# design.net
KiCad netlist of a schematic drawn in Altium Designer
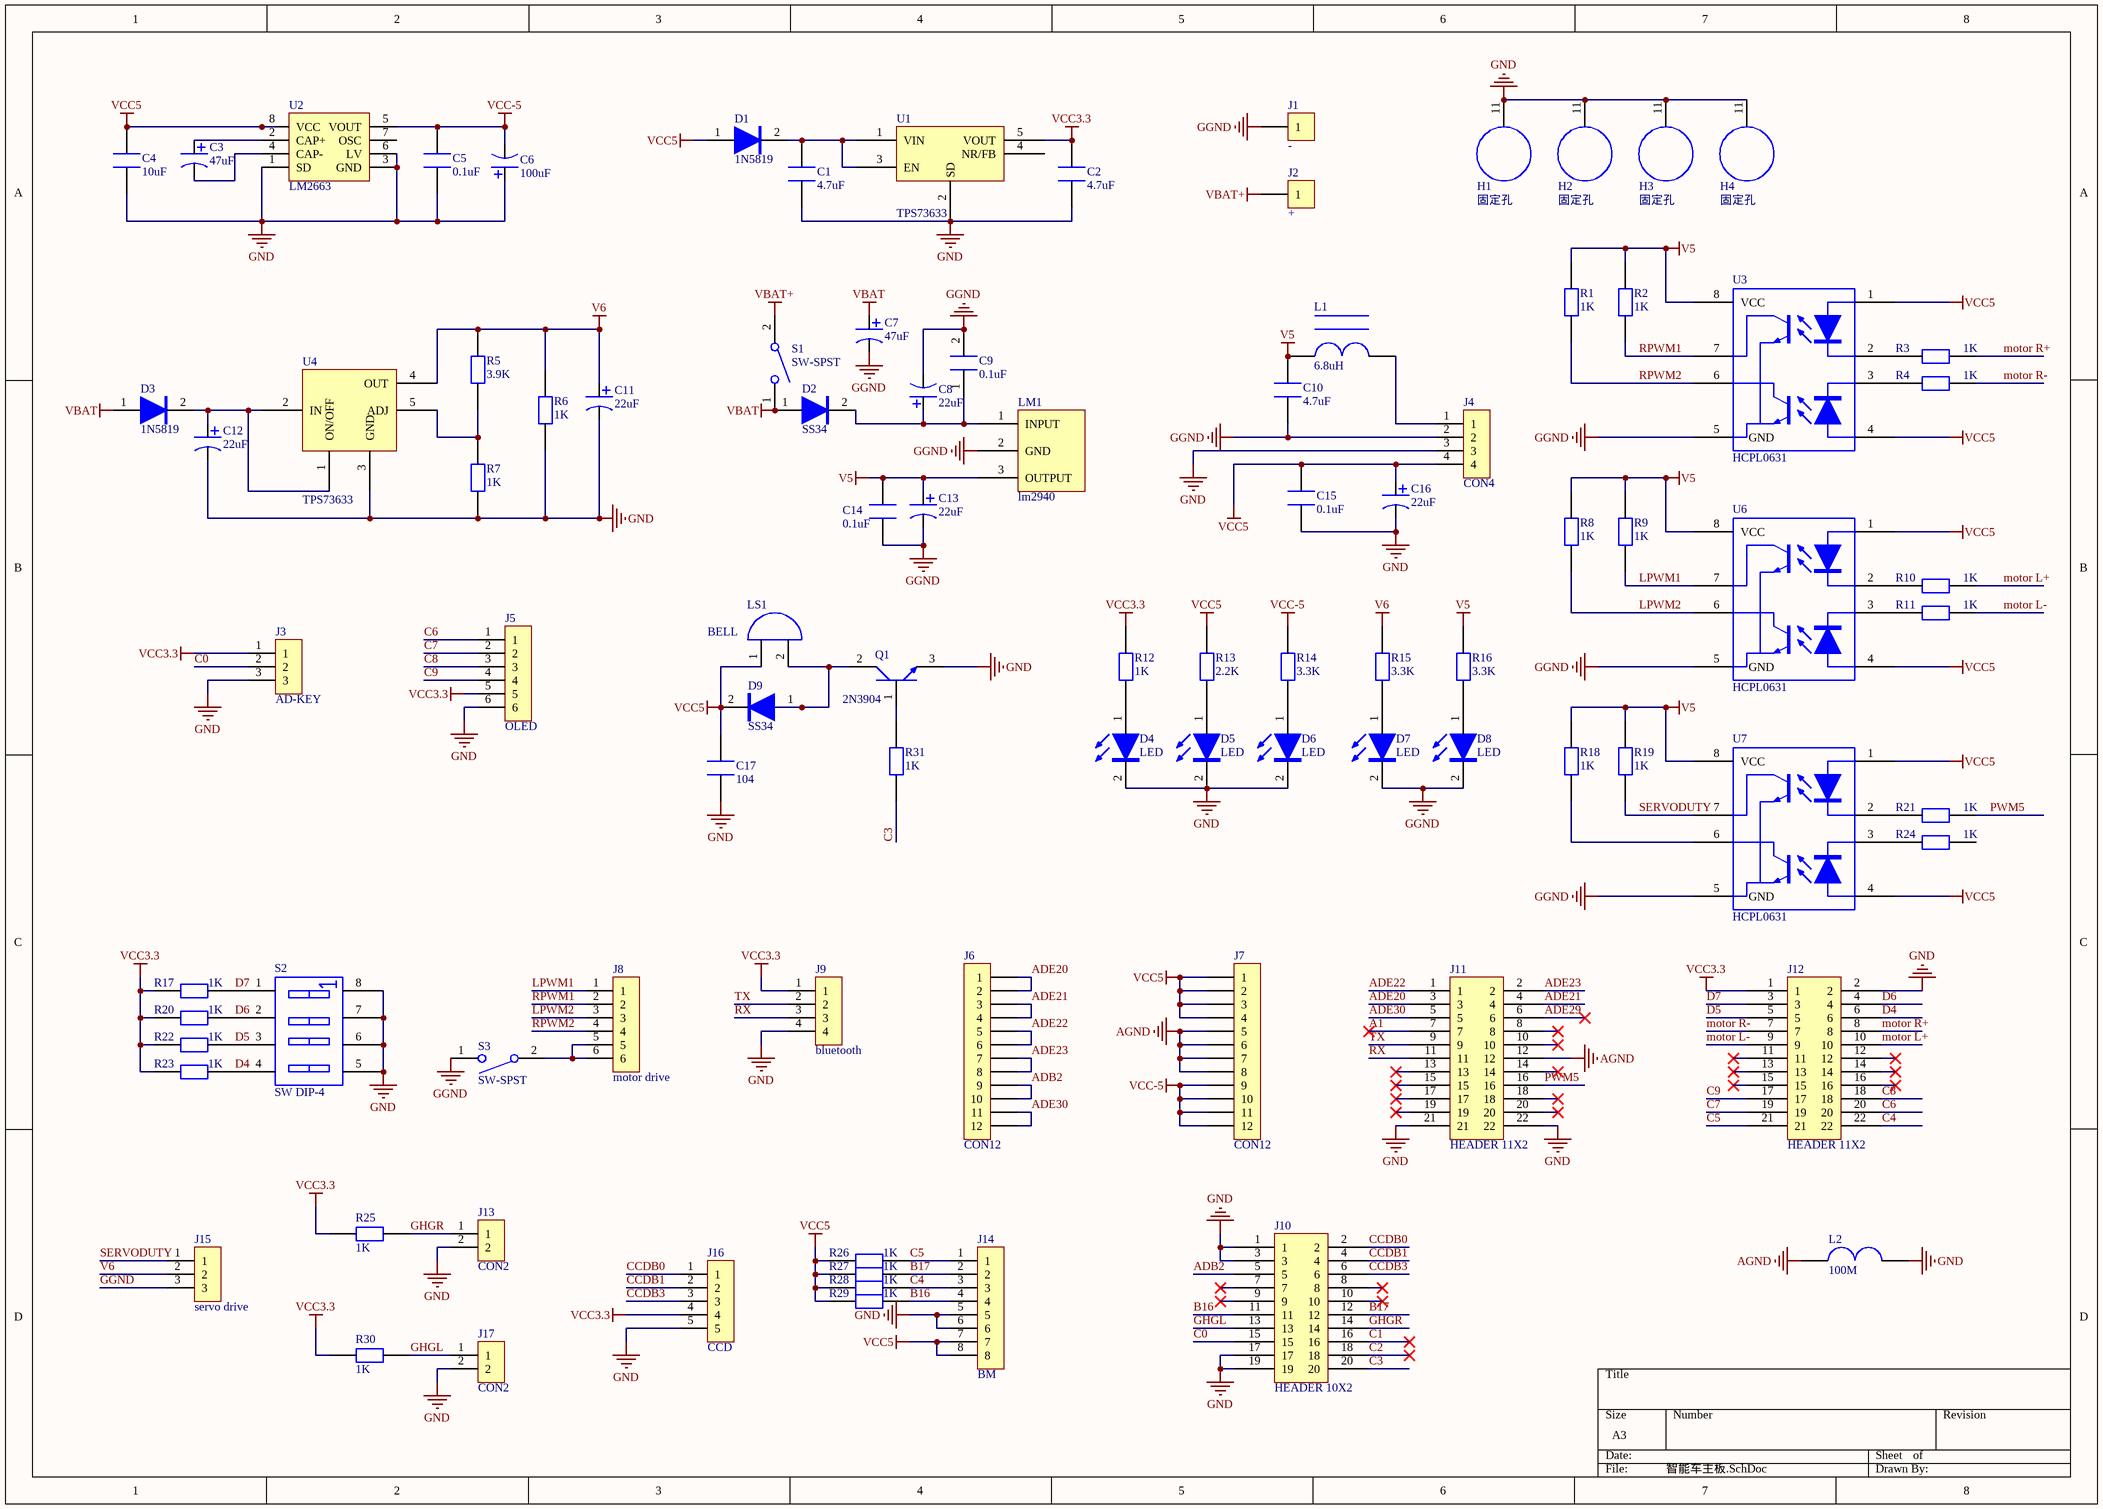
[diagram p0: 智能车主板.SchDoc]

(export (version "E")
  (design (tool "Eeschema 10.0.6"))
  (components
    (comp (ref "C1")
      (value "4.7uF")
      (footprint "0805_Res")
      (description "电容")
      (libsource (lib "智能车主板") (part "CAP"))
    )
    (comp (ref "C2")
      (value "4.7uF")
      (footprint "0805_Res")
      (description "电容")
      (libsource (lib "智能车主板") (part "CAP"))
    )
    (comp (ref "C3")
      (value "47uF")
      (footprint "C型钽电容_6032_28")
      (description "极性电容")
      (libsource (lib "智能车主板") (part "极性电容"))
    )
    (comp (ref "C4")
      (value "10uF")
      (footprint "0805_Res")
      (description "电容")
      (libsource (lib "智能车主板") (part "CAP"))
    )
    (comp (ref "C5")
      (value "0.1uF")
      (footprint "0805_Res")
      (description "电容")
      (libsource (lib "智能车主板") (part "CAP"))
    )
    (comp (ref "C6")
      (value "100uF")
      (footprint "D型钽电容_7343_31")
      (description "极性电容")
      (libsource (lib "智能车主板") (part "极性电容"))
    )
    (comp (ref "C7")
      (value "47uF")
      (footprint "D型钽电容_7343_31")
      (description "极性电容")
      (libsource (lib "智能车主板") (part "极性电容"))
    )
    (comp (ref "C8")
      (value "22uF")
      (footprint "C型钽电容_6032_28")
      (description "极性电容")
      (libsource (lib "智能车主板") (part "极性电容"))
    )
    (comp (ref "C9")
      (value "0.1uF")
      (footprint "0805_Res")
      (description "电容")
      (libsource (lib "") (part "CAP_1"))
    )
    (comp (ref "C10")
      (value "4.7uF")
      (footprint "0805_Res")
      (description "电容")
      (libsource (lib "智能车主板") (part "CAP"))
    )
    (comp (ref "C11")
      (value "22uF")
      (footprint "D型钽电容_7343_31")
      (description "极性电容")
      (libsource (lib "智能车主板") (part "极性电容"))
    )
    (comp (ref "C12")
      (value "22uF")
      (footprint "D型钽电容_7343_31")
      (description "极性电容")
      (libsource (lib "智能车主板") (part "极性电容"))
    )
    (comp (ref "C13")
      (value "22uF")
      (footprint "D型钽电容_7343_31")
      (description "极性电容")
      (libsource (lib "智能车主板") (part "极性电容"))
    )
    (comp (ref "C14")
      (value "0.1uF")
      (footprint "0805_Res")
      (description "电容")
      (libsource (lib "智能车主板") (part "CAP"))
    )
    (comp (ref "C15")
      (value "0.1uF")
      (footprint "0805_Res")
      (description "电容")
      (libsource (lib "智能车主板") (part "CAP"))
    )
    (comp (ref "C16")
      (value "22uF")
      (footprint "D型钽电容_7343_31")
      (description "极性电容")
      (libsource (lib "智能车主板") (part "极性电容"))
    )
    (comp (ref "C17")
      (value "104")
      (footprint "0805_RES")
      (description "电容")
      (libsource (lib "智能车主板") (part "CAP"))
    )
    (comp (ref "D1")
      (value "1N5819")
      (footprint "0805_Dio")
      (description "二极管")
      (libsource (lib "智能车主板") (part "SS34"))
    )
    (comp (ref "D2")
      (value "SS34")
      (footprint "0805_Dio")
      (description "二极管")
      (libsource (lib "智能车主板") (part "SS34"))
    )
    (comp (ref "D3")
      (value "1N5819")
      (footprint "0805_Dio")
      (description "二极管")
      (libsource (lib "智能车主板") (part "SS34"))
    )
    (comp (ref "D4")
      (value "LED")
      (footprint "0805_Dio")
      (description "LED灯")
      (libsource (lib "智能车主板") (part "LED"))
    )
    (comp (ref "D5")
      (value "LED")
      (footprint "0805_Dio")
      (description "LED灯")
      (libsource (lib "智能车主板") (part "LED"))
    )
    (comp (ref "D6")
      (value "LED")
      (footprint "0805_Dio")
      (description "LED灯")
      (libsource (lib "智能车主板") (part "LED"))
    )
    (comp (ref "D7")
      (value "LED")
      (footprint "0805_Dio")
      (description "LED灯")
      (libsource (lib "智能车主板") (part "LED"))
    )
    (comp (ref "D8")
      (value "LED")
      (footprint "0805_Dio")
      (description "LED灯")
      (libsource (lib "智能车主板") (part "LED"))
    )
    (comp (ref "D9")
      (value "SS34")
      (footprint "SS34_3D")
      (description "二极管")
      (libsource (lib "智能车主板") (part "SS34"))
    )
    (comp (ref "H1") (value "固定孔") (footprint "铜柱孔3") (libsource (lib "智能车主板") (part "固定孔")))
    (comp (ref "H2") (value "固定孔") (footprint "铜柱孔3") (libsource (lib "智能车主板") (part "固定孔")))
    (comp (ref "H3") (value "固定孔") (footprint "铜柱孔3") (libsource (lib "智能车主板") (part "固定孔")))
    (comp (ref "H4") (value "固定孔") (footprint "铜柱孔3") (libsource (lib "智能车主板") (part "固定孔")))
    (comp (ref "J1")
      (value "-")
      (footprint "单面焊盘2*3MM_1PIN")
      (description "排针")
      (libsource (lib "智能车主板") (part "CON1"))
    )
    (comp (ref "J2")
      (value "+")
      (footprint "单面焊盘2*3MM_1PIN")
      (description "排针")
      (libsource (lib "智能车主板") (part "CON1"))
    )
    (comp (ref "J3")
      (value "AD-KEY")
      (footprint "HDR1X3")
      (description "排针")
      (libsource (lib "智能车主板") (part "CON3"))
    )
    (comp (ref "J4")
      (value "CON4")
      (footprint "B0505S-2W")
      (description "排针")
      (libsource (lib "智能车主板") (part "CON4"))
    )
    (comp (ref "J5")
      (value "OLED")
      (footprint "HDR1X6")
      (description "排针")
      (libsource (lib "智能车主板") (part "CON6"))
    )
    (comp (ref "J6")
      (value "CON12")
      (footprint "HDR2X6")
      (description "排针")
      (libsource (lib "智能车主板") (part "CON12"))
    )
    (comp (ref "J7")
      (value "CON12")
      (footprint "HDR2X6")
      (description "排针")
      (libsource (lib "") (part "CON12_1"))
    )
    (comp (ref "J8")
      (value "motor drive")
      (footprint "HDR2X3")
      (description "排针")
      (libsource (lib "智能车主板") (part "CON6"))
    )
    (comp (ref "J9")
      (value "bluetooth")
      (footprint "HDR1X4")
      (description "排针")
      (libsource (lib "智能车主板") (part "CON4"))
    )
    (comp (ref "J10")
      (value "HEADER 10X2")
      (footprint "HDR2X10")
      (description "排针")
      (libsource (lib "智能车主板") (part "HEADER 10X2"))
    )
    (comp (ref "J11")
      (value "HEADER 11X2")
      (footprint "HDR2X11")
      (description "排针")
      (libsource (lib "智能车主板") (part "HEADER 11X2"))
    )
    (comp (ref "J12")
      (value "HEADER 11X2")
      (footprint "HDR2X11")
      (description "排针")
      (libsource (lib "智能车主板") (part "HEADER 11X2"))
    )
    (comp (ref "J13")
      (value "CON2")
      (footprint "2PIN杜邦插座_1.27mm")
      (description "排针")
      (libsource (lib "智能车主板") (part "CON2"))
    )
    (comp (ref "J14")
      (value "BM")
      (footprint "HDR2X4")
      (description "排针")
      (libsource (lib "智能车主板") (part "CON8"))
    )
    (comp (ref "J15")
      (value "servo drive")
      (footprint "HDR1X3")
      (description "排针")
      (libsource (lib "智能车主板") (part "CON3"))
    )
    (comp (ref "J16")
      (value "CCD")
      (footprint "HDR1X5")
      (description "排针")
      (libsource (lib "智能车主板") (part "CON5"))
    )
    (comp (ref "J17")
      (value "CON2")
      (footprint "2PIN杜邦插座_1.27mm")
      (description "排针")
      (libsource (lib "智能车主板") (part "CON2"))
    )
    (comp (ref "L1")
      (value "6.8uH")
      (footprint "CDRH3D16_4.2*1.8")
      (description "电感")
      (libsource (lib "智能车主板") (part "INDUCTOR"))
    )
    (comp (ref "L2")
      (value "100M")
      (footprint "0603_Res")
      (description "电感")
      (libsource (lib "智能车主板") (part "INDUCTOR_2"))
    )
    (comp (ref "LM1")
      (value "lm2940")
      (footprint "SOT-223")
      (description "IC")
      (libsource (lib "智能车主板") (part "lm2940"))
    )
    (comp (ref "LS1")
      (value "BELL")
      (footprint "蜂鸣器侧装")
      (description "喇叭")
      (libsource (lib "智能车主板") (part "BELL"))
    )
    (comp (ref "Q1")
      (value "2N3904")
      (footprint "TO-92A")
      (description "三极管")
      (libsource (lib "智能车主板") (part "2N3904"))
    )
    (comp (ref "R1")
      (value "1K")
      (footprint "0805_Res")
      (description "电阻")
      (libsource (lib "智能车主板") (part "RES"))
    )
    (comp (ref "R2")
      (value "1K")
      (footprint "0805_Res")
      (description "电阻")
      (libsource (lib "智能车主板") (part "RES"))
    )
    (comp (ref "R3")
      (value "1K")
      (footprint "0805_Res")
      (description "电阻")
      (libsource (lib "智能车主板") (part "RES"))
    )
    (comp (ref "R4")
      (value "1K")
      (footprint "0805_Res")
      (description "电阻")
      (libsource (lib "智能车主板") (part "RES"))
    )
    (comp (ref "R5")
      (value "3.9K")
      (footprint "0805_Res")
      (description "电阻")
      (libsource (lib "智能车主板") (part "RES"))
    )
    (comp (ref "R6")
      (value "1K")
      (footprint "0805_Res")
      (description "电阻")
      (libsource (lib "智能车主板") (part "RES"))
    )
    (comp (ref "R7")
      (value "1K")
      (footprint "0805_Res")
      (description "电阻")
      (libsource (lib "智能车主板") (part "RES"))
    )
    (comp (ref "R8")
      (value "1K")
      (footprint "0805_Res")
      (description "电阻")
      (libsource (lib "智能车主板") (part "RES"))
    )
    (comp (ref "R9")
      (value "1K")
      (footprint "0805_Res")
      (description "电阻")
      (libsource (lib "智能车主板") (part "RES"))
    )
    (comp (ref "R10")
      (value "1K")
      (footprint "0805_Res")
      (description "电阻")
      (libsource (lib "智能车主板") (part "RES"))
    )
    (comp (ref "R11")
      (value "1K")
      (footprint "0805_Res")
      (description "电阻")
      (libsource (lib "智能车主板") (part "RES"))
    )
    (comp (ref "R12")
      (value "1K")
      (footprint "0603_Res")
      (description "电阻")
      (libsource (lib "智能车主板") (part "RES"))
    )
    (comp (ref "R13")
      (value "2.2K")
      (footprint "0603_Res")
      (description "电阻")
      (libsource (lib "智能车主板") (part "RES"))
    )
    (comp (ref "R14")
      (value "3.3K")
      (footprint "0603_Res")
      (description "电阻")
      (libsource (lib "智能车主板") (part "RES"))
    )
    (comp (ref "R15")
      (value "3.3K")
      (footprint "0603_Res")
      (description "电阻")
      (libsource (lib "智能车主板") (part "RES"))
    )
    (comp (ref "R16")
      (value "3.3K")
      (footprint "0603_Res")
      (description "电阻")
      (libsource (lib "智能车主板") (part "RES"))
    )
    (comp (ref "R17")
      (value "1K")
      (footprint "0603_Res")
      (description "电阻")
      (libsource (lib "智能车主板") (part "RES"))
    )
    (comp (ref "R18")
      (value "1K")
      (footprint "0805_Res")
      (description "电阻")
      (libsource (lib "智能车主板") (part "RES"))
    )
    (comp (ref "R19")
      (value "1K")
      (footprint "0805_Res")
      (description "电阻")
      (libsource (lib "智能车主板") (part "RES"))
    )
    (comp (ref "R20")
      (value "1K")
      (footprint "0603_Res")
      (description "电阻")
      (libsource (lib "智能车主板") (part "RES"))
    )
    (comp (ref "R21")
      (value "1K")
      (footprint "0805_Res")
      (description "电阻")
      (libsource (lib "智能车主板") (part "RES"))
    )
    (comp (ref "R22")
      (value "1K")
      (footprint "0603_Res")
      (description "电阻")
      (libsource (lib "智能车主板") (part "RES"))
    )
    (comp (ref "R23")
      (value "1K")
      (footprint "0603_Res")
      (description "电阻")
      (libsource (lib "智能车主板") (part "RES"))
    )
    (comp (ref "R24")
      (value "1K")
      (footprint "0805_Res")
      (description "电阻")
      (libsource (lib "智能车主板") (part "RES"))
    )
    (comp (ref "R25")
      (value "1K")
      (footprint "0603_Res")
      (description "电阻")
      (libsource (lib "智能车主板") (part "RES"))
    )
    (comp (ref "R26")
      (value "1K")
      (footprint "0805_Res")
      (description "电阻")
      (libsource (lib "智能车主板") (part "RES"))
    )
    (comp (ref "R27")
      (value "1K")
      (footprint "0805_Res")
      (description "电阻")
      (libsource (lib "智能车主板") (part "RES"))
    )
    (comp (ref "R28")
      (value "1K")
      (footprint "0805_Res")
      (description "电阻")
      (libsource (lib "智能车主板") (part "RES"))
    )
    (comp (ref "R29")
      (value "1K")
      (footprint "0805_Res")
      (description "电阻")
      (libsource (lib "智能车主板") (part "RES"))
    )
    (comp (ref "R30")
      (value "1K")
      (footprint "0603_Res")
      (description "电阻")
      (libsource (lib "智能车主板") (part "RES"))
    )
    (comp (ref "R31")
      (value "1K")
      (footprint "0805_Res")
      (description "电阻")
      (libsource (lib "智能车主板") (part "RES"))
    )
    (comp (ref "S1")
      (value "SW-SPST")
      (footprint "开关")
      (description "开关")
      (libsource (lib "智能车主板") (part "SW-SPST"))
    )
    (comp (ref "S2")
      (value "SW DIP-4")
      (footprint "4路拨码开关")
      (description "拨码开关")
      (libsource (lib "智能车主板") (part "SW DIP-4"))
    )
    (comp (ref "S3")
      (value "SW-SPST")
      (footprint "开关")
      (description "开关")
      (libsource (lib "智能车主板") (part "SW-SPST"))
    )
    (comp (ref "U1")
      (value "TPS73633")
      (footprint "SOT23_5-LEADS")
      (description "IC")
      (libsource (lib "智能车主板") (part "TPS73633"))
    )
    (comp (ref "U2")
      (value "LM2663")
      (footprint "SOP_8(OPA)")
      (description "IC")
      (libsource (lib "智能车主板") (part "LM2663"))
    )
    (comp (ref "U3")
      (value "HCPL0631")
      (footprint "SOP_8(OPA)")
      (description "光耦")
      (libsource (lib "智能车主板") (part "HCPL0631"))
    )
    (comp (ref "U4")
      (value "TPS73633")
      (footprint "TO_263_5(10.5*8.4mm)")
      (description "IC")
      (libsource (lib "智能车主板") (part "MIC29302"))
    )
    (comp (ref "U6")
      (value "HCPL0631")
      (footprint "SOP_8(OPA)")
      (description "光耦")
      (libsource (lib "智能车主板") (part "HCPL0631"))
    )
    (comp (ref "U7")
      (value "HCPL0631")
      (footprint "SOP_8(OPA)")
      (description "光耦")
      (libsource (lib "智能车主板") (part "HCPL0631"))
    )
  )
  (nets
    (net (code "1") (name "/A1") (class "Default")
      (node (ref "J11") (pin "7") (pinfunction "7_7") (pintype "passive+no_connect"))
    )
    (net (code "2") (name "/ADB2") (class "Default")
      (node (ref "J10") (pin "5") (pinfunction "5_5") (pintype "passive"))
      (node (ref "J6") (pin "10") (pinfunction "10_10") (pintype "passive"))
      (node (ref "J6") (pin "9") (pinfunction "9_9") (pintype "passive"))
    )
    (net (code "3") (name "/ADE20") (class "Default")
      (node (ref "J11") (pin "3") (pinfunction "3_3") (pintype "passive"))
      (node (ref "J6") (pin "1") (pinfunction "1_1") (pintype "passive"))
      (node (ref "J6") (pin "2") (pinfunction "2_2") (pintype "passive"))
    )
    (net (code "4") (name "/ADE21") (class "Default")
      (node (ref "J11") (pin "4") (pinfunction "4_4") (pintype "passive"))
      (node (ref "J6") (pin "3") (pinfunction "3_3") (pintype "passive"))
      (node (ref "J6") (pin "4") (pinfunction "4_4") (pintype "passive"))
    )
    (net (code "5") (name "/ADE22") (class "Default")
      (node (ref "J11") (pin "1") (pinfunction "1_1") (pintype "passive"))
      (node (ref "J6") (pin "5") (pinfunction "5_5") (pintype "passive"))
      (node (ref "J6") (pin "6") (pinfunction "6_6") (pintype "passive"))
    )
    (net (code "6") (name "/ADE23") (class "Default")
      (node (ref "J11") (pin "2") (pinfunction "2_2") (pintype "passive"))
      (node (ref "J6") (pin "7") (pinfunction "7_7") (pintype "passive"))
      (node (ref "J6") (pin "8") (pinfunction "8_8") (pintype "passive"))
    )
    (net (code "7") (name "/ADE29") (class "Default")
      (node (ref "J11") (pin "6") (pinfunction "6_6") (pintype "passive+no_connect"))
    )
    (net (code "8") (name "/ADE30") (class "Default")
      (node (ref "J11") (pin "5") (pinfunction "5_5") (pintype "passive"))
      (node (ref "J6") (pin "11") (pinfunction "11_11") (pintype "passive"))
      (node (ref "J6") (pin "12") (pinfunction "12_12") (pintype "passive"))
    )
    (net (code "9") (name "/B16") (class "Default")
      (node (ref "J10") (pin "11") (pinfunction "11_11") (pintype "passive"))
      (node (ref "J14") (pin "4") (pinfunction "4_4") (pintype "passive"))
      (node (ref "R29") (pin "2") (pinfunction "2_2") (pintype "passive"))
    )
    (net (code "10") (name "/B17") (class "Default")
      (node (ref "J10") (pin "12") (pinfunction "12_12") (pintype "passive"))
      (node (ref "J14") (pin "2") (pinfunction "2_2") (pintype "passive"))
      (node (ref "R27") (pin "2") (pinfunction "2_2") (pintype "passive"))
    )
    (net (code "11") (name "/C0") (class "Default")
      (node (ref "J10") (pin "15") (pinfunction "15_15") (pintype "passive"))
      (node (ref "J3") (pin "2") (pinfunction "2_2") (pintype "passive"))
    )
    (net (code "12") (name "/C1") (class "Default")
      (node (ref "J10") (pin "16") (pinfunction "16_16") (pintype "passive+no_connect"))
    )
    (net (code "13") (name "/C2") (class "Default")
      (node (ref "J10") (pin "18") (pinfunction "18_18") (pintype "passive+no_connect"))
    )
    (net (code "14") (name "/C3") (class "Default")
      (node (ref "J10") (pin "20") (pinfunction "20_20") (pintype "passive"))
      (node (ref "R31") (pin "1") (pinfunction "1_1") (pintype "passive"))
    )
    (net (code "15") (name "/C4") (class "Default")
      (node (ref "J12") (pin "22") (pinfunction "22_22") (pintype "passive"))
      (node (ref "J14") (pin "3") (pinfunction "3_3") (pintype "passive"))
      (node (ref "R28") (pin "2") (pinfunction "2_2") (pintype "passive"))
    )
    (net (code "16") (name "/C5") (class "Default")
      (node (ref "J12") (pin "21") (pinfunction "21_21") (pintype "passive"))
      (node (ref "J14") (pin "1") (pinfunction "1_1") (pintype "passive"))
      (node (ref "R26") (pin "2") (pinfunction "2_2") (pintype "passive"))
    )
    (net (code "17") (name "/C6") (class "Default")
      (node (ref "J12") (pin "20") (pinfunction "20_20") (pintype "passive"))
      (node (ref "J5") (pin "1") (pinfunction "1_1") (pintype "passive"))
    )
    (net (code "18") (name "/C7") (class "Default")
      (node (ref "J12") (pin "19") (pinfunction "19_19") (pintype "passive"))
      (node (ref "J5") (pin "2") (pinfunction "2_2") (pintype "passive"))
    )
    (net (code "19") (name "/C8") (class "Default")
      (node (ref "J12") (pin "18") (pinfunction "18_18") (pintype "passive"))
      (node (ref "J5") (pin "3") (pinfunction "3_3") (pintype "passive"))
    )
    (net (code "20") (name "/C9") (class "Default")
      (node (ref "J12") (pin "17") (pinfunction "17_17") (pintype "passive"))
      (node (ref "J5") (pin "4") (pinfunction "4_4") (pintype "passive"))
    )
    (net (code "21") (name "/CCDB0") (class "Default")
      (node (ref "J10") (pin "2") (pinfunction "2_2") (pintype "passive"))
      (node (ref "J16") (pin "1") (pinfunction "1_1") (pintype "passive"))
    )
    (net (code "22") (name "/CCDB1") (class "Default")
      (node (ref "J10") (pin "4") (pinfunction "4_4") (pintype "passive"))
      (node (ref "J16") (pin "2") (pinfunction "2_2") (pintype "passive"))
    )
    (net (code "23") (name "/CCDB3") (class "Default")
      (node (ref "J10") (pin "6") (pinfunction "6_6") (pintype "passive"))
      (node (ref "J16") (pin "3") (pinfunction "3_3") (pintype "passive"))
    )
    (net (code "24") (name "/D4") (class "Default")
      (node (ref "J12") (pin "6") (pinfunction "6_6") (pintype "passive"))
      (node (ref "R23") (pin "1") (pinfunction "1_1") (pintype "passive"))
      (node (ref "S2") (pin "4") (pinfunction "4_4") (pintype "passive"))
    )
    (net (code "25") (name "/D5") (class "Default")
      (node (ref "J12") (pin "5") (pinfunction "5_5") (pintype "passive"))
      (node (ref "R22") (pin "1") (pinfunction "1_1") (pintype "passive"))
      (node (ref "S2") (pin "3") (pinfunction "3_3") (pintype "passive"))
    )
    (net (code "26") (name "/D6") (class "Default")
      (node (ref "J12") (pin "4") (pinfunction "4_4") (pintype "passive"))
      (node (ref "R20") (pin "1") (pinfunction "1_1") (pintype "passive"))
      (node (ref "S2") (pin "2") (pinfunction "2_2") (pintype "passive"))
    )
    (net (code "27") (name "/D7") (class "Default")
      (node (ref "J12") (pin "3") (pinfunction "3_3") (pintype "passive"))
      (node (ref "R17") (pin "1") (pinfunction "1_1") (pintype "passive"))
      (node (ref "S2") (pin "1") (pinfunction "1_1") (pintype "passive"))
    )
    (net (code "28") (name "/GHGL") (class "Default")
      (node (ref "J10") (pin "13") (pinfunction "13_13") (pintype "passive"))
      (node (ref "J17") (pin "1") (pinfunction "1_1") (pintype "passive"))
      (node (ref "R30") (pin "2") (pinfunction "2_2") (pintype "passive"))
    )
    (net (code "29") (name "/GHGR") (class "Default")
      (node (ref "J10") (pin "14") (pinfunction "14_14") (pintype "passive"))
      (node (ref "J13") (pin "1") (pinfunction "1_1") (pintype "passive"))
      (node (ref "R25") (pin "2") (pinfunction "2_2") (pintype "passive"))
    )
    (net (code "30") (name "/LPWM1") (class "Default")
      (node (ref "J8") (pin "1") (pinfunction "1_1") (pintype "passive"))
      (node (ref "R9") (pin "1") (pinfunction "1_1") (pintype "passive"))
      (node (ref "U6") (pin "7") (pinfunction "7_7") (pintype "passive"))
    )
    (net (code "31") (name "/LPWM2") (class "Default")
      (node (ref "J8") (pin "3") (pinfunction "3_3") (pintype "passive"))
      (node (ref "R8") (pin "1") (pinfunction "1_1") (pintype "passive"))
      (node (ref "U6") (pin "6") (pinfunction "6_6") (pintype "passive"))
    )
    (net (code "32") (name "/PWM5") (class "Default")
      (node (ref "J11") (pin "16") (pinfunction "16_16") (pintype "passive"))
      (node (ref "R21") (pin "1") (pinfunction "1_1") (pintype "passive"))
    )
    (net (code "33") (name "/RPWM1") (class "Default")
      (node (ref "J8") (pin "2") (pinfunction "2_2") (pintype "passive"))
      (node (ref "R2") (pin "1") (pinfunction "1_1") (pintype "passive"))
      (node (ref "U3") (pin "7") (pinfunction "7_7") (pintype "passive"))
    )
    (net (code "34") (name "/RPWM2") (class "Default")
      (node (ref "J8") (pin "4") (pinfunction "4_4") (pintype "passive"))
      (node (ref "R1") (pin "1") (pinfunction "1_1") (pintype "passive"))
      (node (ref "U3") (pin "6") (pinfunction "6_6") (pintype "passive"))
    )
    (net (code "35") (name "/RX") (class "Default")
      (node (ref "J11") (pin "11") (pinfunction "11_11") (pintype "passive"))
      (node (ref "J9") (pin "3") (pinfunction "3_3") (pintype "passive"))
    )
    (net (code "36") (name "/SERVODUTY") (class "Default")
      (node (ref "J15") (pin "1") (pinfunction "1_1") (pintype "passive"))
      (node (ref "R19") (pin "1") (pinfunction "1_1") (pintype "passive"))
      (node (ref "U7") (pin "7") (pinfunction "7_7") (pintype "passive"))
    )
    (net (code "37") (name "/TX") (class "Default")
      (node (ref "J11") (pin "9") (pinfunction "9_9") (pintype "passive"))
      (node (ref "J9") (pin "2") (pinfunction "2_2") (pintype "passive"))
    )
    (net (code "38") (name "/motor L+") (class "Default")
      (node (ref "J12") (pin "10") (pinfunction "10_10") (pintype "passive"))
      (node (ref "R10") (pin "1") (pinfunction "1_1") (pintype "passive"))
    )
    (net (code "39") (name "/motor L-") (class "Default")
      (node (ref "J12") (pin "9") (pinfunction "9_9") (pintype "passive"))
      (node (ref "R11") (pin "1") (pinfunction "1_1") (pintype "passive"))
    )
    (net (code "40") (name "/motor R+") (class "Default")
      (node (ref "J12") (pin "8") (pinfunction "8_8") (pintype "passive"))
      (node (ref "R3") (pin "1") (pinfunction "1_1") (pintype "passive"))
    )
    (net (code "41") (name "/motor R-") (class "Default")
      (node (ref "J12") (pin "7") (pinfunction "7_7") (pintype "passive"))
      (node (ref "R4") (pin "1") (pinfunction "1_1") (pintype "passive"))
    )
    (net (code "42") (name "AGND") (class "Default")
      (node (ref "J11") (pin "12") (pinfunction "12_12") (pintype "passive"))
      (node (ref "J7") (pin "5") (pinfunction "5_5") (pintype "passive"))
      (node (ref "J7") (pin "6") (pinfunction "6_6") (pintype "passive"))
      (node (ref "J7") (pin "7") (pinfunction "7_7") (pintype "passive"))
      (node (ref "J7") (pin "8") (pinfunction "8_8") (pintype "passive"))
      (node (ref "L2") (pin "1") (pinfunction "1_1") (pintype "passive"))
    )
    (net (code "43") (name "GGND") (class "Default")
      (node (ref "C10") (pin "1") (pinfunction "1_1") (pintype "passive"))
      (node (ref "C13") (pin "2") (pinfunction "2_2") (pintype "passive"))
      (node (ref "C14") (pin "1") (pinfunction "1_1") (pintype "passive"))
      (node (ref "C7") (pin "2") (pinfunction "2_2") (pintype "passive"))
      (node (ref "C8") (pin "2") (pinfunction "2_2") (pintype "passive"))
      (node (ref "C9") (pin "2") (pinfunction "2_2") (pintype "passive"))
      (node (ref "D7") (pin "2") (pinfunction "2_2") (pintype "passive"))
      (node (ref "D8") (pin "2") (pinfunction "2_2") (pintype "passive"))
      (node (ref "J1") (pin "1") (pinfunction "1_1") (pintype "passive"))
      (node (ref "J15") (pin "3") (pinfunction "3_3") (pintype "passive"))
      (node (ref "J4") (pin "2") (pinfunction "2_2") (pintype "passive"))
      (node (ref "LM1") (pin "2") (pinfunction "GND_2") (pintype "passive"))
      (node (ref "S3") (pin "1") (pinfunction "1_1") (pintype "passive"))
      (node (ref "U3") (pin "5") (pinfunction "GND_5") (pintype "passive"))
      (node (ref "U6") (pin "5") (pinfunction "GND_5") (pintype "passive"))
      (node (ref "U7") (pin "5") (pinfunction "GND_5") (pintype "passive"))
    )
    (net (code "44") (name "GND") (class "Default")
      (node (ref "C1") (pin "1") (pinfunction "1_1") (pintype "passive"))
      (node (ref "C11") (pin "2") (pinfunction "2_2") (pintype "passive"))
      (node (ref "C12") (pin "2") (pinfunction "2_2") (pintype "passive"))
      (node (ref "C15") (pin "1") (pinfunction "1_1") (pintype "passive"))
      (node (ref "C16") (pin "2") (pinfunction "2_2") (pintype "passive"))
      (node (ref "C17") (pin "1") (pinfunction "1_1") (pintype "passive"))
      (node (ref "C2") (pin "1") (pinfunction "1_1") (pintype "passive"))
      (node (ref "C4") (pin "1") (pinfunction "1_1") (pintype "passive"))
      (node (ref "C5") (pin "1") (pinfunction "1_1") (pintype "passive"))
      (node (ref "C6") (pin "1") (pinfunction "1_1") (pintype "passive"))
      (node (ref "D4") (pin "2") (pinfunction "2_2") (pintype "passive"))
      (node (ref "D5") (pin "2") (pinfunction "2_2") (pintype "passive"))
      (node (ref "D6") (pin "2") (pinfunction "2_2") (pintype "passive"))
      (node (ref "H1") (pin "11") (pinfunction "11_11") (pintype "passive"))
      (node (ref "H2") (pin "11") (pinfunction "11_11") (pintype "passive"))
      (node (ref "H3") (pin "11") (pinfunction "11_11") (pintype "passive"))
      (node (ref "H4") (pin "11") (pinfunction "11_11") (pintype "passive"))
      (node (ref "J10") (pin "1") (pinfunction "1_1") (pintype "passive"))
      (node (ref "J10") (pin "17") (pinfunction "17_17") (pintype "passive"))
      (node (ref "J10") (pin "19") (pinfunction "19_19") (pintype "passive"))
      (node (ref "J10") (pin "3") (pinfunction "3_3") (pintype "passive"))
      (node (ref "J11") (pin "21") (pinfunction "21_21") (pintype "passive"))
      (node (ref "J11") (pin "22") (pinfunction "22_22") (pintype "passive"))
      (node (ref "J12") (pin "2") (pinfunction "2_2") (pintype "passive"))
      (node (ref "J13") (pin "2") (pinfunction "2_2") (pintype "passive"))
      (node (ref "J14") (pin "5") (pinfunction "5_5") (pintype "passive"))
      (node (ref "J14") (pin "6") (pinfunction "6_6") (pintype "passive"))
      (node (ref "J16") (pin "5") (pinfunction "5_5") (pintype "passive"))
      (node (ref "J17") (pin "2") (pinfunction "2_2") (pintype "passive"))
      (node (ref "J3") (pin "3") (pinfunction "3_3") (pintype "passive"))
      (node (ref "J4") (pin "3") (pinfunction "3_3") (pintype "passive"))
      (node (ref "J5") (pin "6") (pinfunction "6_6") (pintype "passive"))
      (node (ref "J9") (pin "4") (pinfunction "4_4") (pintype "passive"))
      (node (ref "L2") (pin "2") (pinfunction "2_2") (pintype "passive"))
      (node (ref "Q1") (pin "3") (pinfunction "3_3") (pintype "passive"))
      (node (ref "R6") (pin "2") (pinfunction "2_2") (pintype "passive"))
      (node (ref "R7") (pin "2") (pinfunction "2_2") (pintype "passive"))
      (node (ref "S2") (pin "5") (pinfunction "5_5") (pintype "passive"))
      (node (ref "S2") (pin "6") (pinfunction "6_6") (pintype "passive"))
      (node (ref "S2") (pin "7") (pinfunction "7_7") (pintype "passive"))
      (node (ref "S2") (pin "8") (pinfunction "8_8") (pintype "passive"))
      (node (ref "U1") (pin "2") (pinfunction "SD_2") (pintype "passive"))
      (node (ref "U2") (pin "1") (pinfunction "SD_1") (pintype "passive"))
      (node (ref "U2") (pin "3") (pinfunction "GND_3") (pintype "passive"))
      (node (ref "U2") (pin "6") (pinfunction "LV_6") (pintype "passive"))
      (node (ref "U4") (pin "3") (pinfunction "GND_3") (pintype "passive"))
    )
    (net (code "45") (name "Net-(D4-Pad1)") (class "Default")
      (node (ref "D4") (pin "1") (pinfunction "1_1") (pintype "passive"))
      (node (ref "R12") (pin "1") (pinfunction "1_1") (pintype "passive"))
    )
    (net (code "46") (name "Net-(D5-Pad1)") (class "Default")
      (node (ref "D5") (pin "1") (pinfunction "1_1") (pintype "passive"))
      (node (ref "R13") (pin "1") (pinfunction "1_1") (pintype "passive"))
    )
    (net (code "47") (name "Net-(D6-Pad1)") (class "Default")
      (node (ref "D6") (pin "1") (pinfunction "1_1") (pintype "passive"))
      (node (ref "R14") (pin "1") (pinfunction "1_1") (pintype "passive"))
    )
    (net (code "48") (name "Net-(D7-Pad1)") (class "Default")
      (node (ref "D7") (pin "1") (pinfunction "1_1") (pintype "passive"))
      (node (ref "R15") (pin "1") (pinfunction "1_1") (pintype "passive"))
    )
    (net (code "49") (name "Net-(D8-Pad1)") (class "Default")
      (node (ref "D8") (pin "1") (pinfunction "1_1") (pintype "passive"))
      (node (ref "R16") (pin "1") (pinfunction "1_1") (pintype "passive"))
    )
    (net (code "50") (name "Net-(D9-Pad1)") (class "Default")
      (node (ref "D9") (pin "1") (pinfunction "1_1") (pintype "passive"))
      (node (ref "LS1") (pin "2") (pinfunction "2_2") (pintype "passive"))
      (node (ref "Q1") (pin "2") (pinfunction "2_2") (pintype "passive"))
    )
    (net (code "51") (name "Net-(J4-Pad1)") (class "Default")
      (node (ref "J4") (pin "1") (pinfunction "1_1") (pintype "passive"))
      (node (ref "L1") (pin "2") (pinfunction "2_2") (pintype "passive"))
    )
    (net (code "52") (name "Net-(J8-Pad5)") (class "Default")
      (node (ref "J8") (pin "5") (pinfunction "5_5") (pintype "passive"))
      (node (ref "J8") (pin "6") (pinfunction "6_6") (pintype "passive"))
      (node (ref "S3") (pin "2") (pinfunction "2_2") (pintype "passive"))
    )
    (net (code "53") (name "Net-(LM1-INPUT)") (class "Default")
      (node (ref "C8") (pin "1") (pinfunction "1_1") (pintype "passive"))
      (node (ref "C9") (pin "1") (pinfunction "1_1") (pintype "passive"))
      (node (ref "D2") (pin "2") (pinfunction "2_2") (pintype "passive"))
      (node (ref "LM1") (pin "1") (pinfunction "INPUT_1") (pintype "passive"))
    )
    (net (code "54") (name "Net-(Q1-Pad1)") (class "Default")
      (node (ref "Q1") (pin "1") (pinfunction "1_1") (pintype "passive"))
      (node (ref "R31") (pin "2") (pinfunction "2_2") (pintype "passive"))
    )
    (net (code "55") (name "Net-(R3-Pad2)") (class "Default")
      (node (ref "R3") (pin "2") (pinfunction "2_2") (pintype "passive"))
      (node (ref "U3") (pin "2") (pinfunction "2_2") (pintype "passive"))
    )
    (net (code "56") (name "Net-(R4-Pad2)") (class "Default")
      (node (ref "R4") (pin "2") (pinfunction "2_2") (pintype "passive"))
      (node (ref "U3") (pin "3") (pinfunction "3_3") (pintype "passive"))
    )
    (net (code "57") (name "Net-(R10-Pad2)") (class "Default")
      (node (ref "R10") (pin "2") (pinfunction "2_2") (pintype "passive"))
      (node (ref "U6") (pin "2") (pinfunction "2_2") (pintype "passive"))
    )
    (net (code "58") (name "Net-(R11-Pad2)") (class "Default")
      (node (ref "R11") (pin "2") (pinfunction "2_2") (pintype "passive"))
      (node (ref "U6") (pin "3") (pinfunction "3_3") (pintype "passive"))
    )
    (net (code "59") (name "Net-(R18-Pad1)") (class "Default")
      (node (ref "R18") (pin "1") (pinfunction "1_1") (pintype "passive"))
      (node (ref "U7") (pin "6") (pinfunction "6_6") (pintype "passive"))
    )
    (net (code "60") (name "Net-(R21-Pad2)") (class "Default")
      (node (ref "R21") (pin "2") (pinfunction "2_2") (pintype "passive"))
      (node (ref "U7") (pin "2") (pinfunction "2_2") (pintype "passive"))
    )
    (net (code "61") (name "Net-(R24-Pad2)") (class "Default")
      (node (ref "R24") (pin "2") (pinfunction "2_2") (pintype "passive"))
      (node (ref "U7") (pin "3") (pinfunction "3_3") (pintype "passive"))
    )
    (net (code "62") (name "Net-(U1-EN)") (class "Default")
      (node (ref "C1") (pin "2") (pinfunction "2_2") (pintype "passive"))
      (node (ref "D1") (pin "2") (pinfunction "2_2") (pintype "passive"))
      (node (ref "U1") (pin "1") (pinfunction "VIN_1") (pintype "passive"))
      (node (ref "U1") (pin "3") (pinfunction "EN_3") (pintype "passive"))
    )
    (net (code "63") (name "Net-(U2-CAP+)") (class "Default")
      (node (ref "C3") (pin "1") (pinfunction "1_1") (pintype "passive"))
      (node (ref "U2") (pin "2") (pinfunction "CAP+_2") (pintype "passive"))
    )
    (net (code "64") (name "Net-(U2-CAP-)") (class "Default")
      (node (ref "C3") (pin "2") (pinfunction "2_2") (pintype "passive"))
      (node (ref "U2") (pin "4") (pinfunction "CAP-_4") (pintype "passive"))
    )
    (net (code "65") (name "Net-(U4-ADJ)") (class "Default")
      (node (ref "R5") (pin "2") (pinfunction "2_2") (pintype "passive"))
      (node (ref "R7") (pin "1") (pinfunction "1_1") (pintype "passive"))
      (node (ref "U4") (pin "5") (pinfunction "ADJ_5") (pintype "passive"))
    )
    (net (code "66") (name "Net-(U4-IN)") (class "Default")
      (node (ref "C12") (pin "1") (pinfunction "1_1") (pintype "passive"))
      (node (ref "D3") (pin "2") (pinfunction "2_2") (pintype "passive"))
      (node (ref "U4") (pin "1") (pinfunction "ON/OFF_1") (pintype "passive"))
      (node (ref "U4") (pin "2") (pinfunction "IN_2") (pintype "passive"))
    )
    (net (code "67") (name "V5") (class "Default")
      (node (ref "C10") (pin "2") (pinfunction "2_2") (pintype "passive"))
      (node (ref "C13") (pin "1") (pinfunction "1_1") (pintype "passive"))
      (node (ref "C14") (pin "2") (pinfunction "2_2") (pintype "passive"))
      (node (ref "L1") (pin "1") (pinfunction "1_1") (pintype "passive"))
      (node (ref "LM1") (pin "3") (pinfunction "OUTPUT_3") (pintype "passive"))
      (node (ref "R1") (pin "2") (pinfunction "2_2") (pintype "passive"))
      (node (ref "R16") (pin "2") (pinfunction "2_2") (pintype "passive"))
      (node (ref "R18") (pin "2") (pinfunction "2_2") (pintype "passive"))
      (node (ref "R19") (pin "2") (pinfunction "2_2") (pintype "passive"))
      (node (ref "R2") (pin "2") (pinfunction "2_2") (pintype "passive"))
      (node (ref "R8") (pin "2") (pinfunction "2_2") (pintype "passive"))
      (node (ref "R9") (pin "2") (pinfunction "2_2") (pintype "passive"))
      (node (ref "U3") (pin "8") (pinfunction "VCC_8") (pintype "passive"))
      (node (ref "U6") (pin "8") (pinfunction "VCC_8") (pintype "passive"))
      (node (ref "U7") (pin "8") (pinfunction "VCC_8") (pintype "passive"))
    )
    (net (code "68") (name "V6") (class "Default")
      (node (ref "C11") (pin "1") (pinfunction "1_1") (pintype "passive"))
      (node (ref "J15") (pin "2") (pinfunction "2_2") (pintype "passive"))
      (node (ref "R15") (pin "2") (pinfunction "2_2") (pintype "passive"))
      (node (ref "R5") (pin "1") (pinfunction "1_1") (pintype "passive"))
      (node (ref "R6") (pin "1") (pinfunction "1_1") (pintype "passive"))
      (node (ref "U4") (pin "4") (pinfunction "OUT_4") (pintype "passive"))
    )
    (net (code "69") (name "VBAT") (class "Default")
      (node (ref "C7") (pin "1") (pinfunction "1_1") (pintype "passive"))
      (node (ref "D2") (pin "1") (pinfunction "1_1") (pintype "passive"))
      (node (ref "D3") (pin "1") (pinfunction "1_1") (pintype "passive"))
      (node (ref "S1") (pin "1") (pinfunction "1_1") (pintype "passive"))
    )
    (net (code "70") (name "VBAT+") (class "Default")
      (node (ref "J2") (pin "1") (pinfunction "1_1") (pintype "passive"))
      (node (ref "S1") (pin "2") (pinfunction "2_2") (pintype "passive"))
    )
    (net (code "71") (name "VCC-5") (class "Default")
      (node (ref "C5") (pin "2") (pinfunction "2_2") (pintype "passive"))
      (node (ref "C6") (pin "2") (pinfunction "2_2") (pintype "passive"))
      (node (ref "J7") (pin "10") (pinfunction "10_10") (pintype "passive"))
      (node (ref "J7") (pin "11") (pinfunction "11_11") (pintype "passive"))
      (node (ref "J7") (pin "12") (pinfunction "12_12") (pintype "passive"))
      (node (ref "J7") (pin "9") (pinfunction "9_9") (pintype "passive"))
      (node (ref "R14") (pin "2") (pinfunction "2_2") (pintype "passive"))
      (node (ref "U2") (pin "5") (pinfunction "VOUT_5") (pintype "passive"))
    )
    (net (code "72") (name "VCC3.3") (class "Default")
      (node (ref "C2") (pin "2") (pinfunction "2_2") (pintype "passive"))
      (node (ref "J12") (pin "1") (pinfunction "1_1") (pintype "passive"))
      (node (ref "J16") (pin "4") (pinfunction "4_4") (pintype "passive"))
      (node (ref "J3") (pin "1") (pinfunction "1_1") (pintype "passive"))
      (node (ref "J5") (pin "5") (pinfunction "5_5") (pintype "passive"))
      (node (ref "J9") (pin "1") (pinfunction "1_1") (pintype "passive"))
      (node (ref "R12") (pin "2") (pinfunction "2_2") (pintype "passive"))
      (node (ref "R17") (pin "2") (pinfunction "2_2") (pintype "passive"))
      (node (ref "R20") (pin "2") (pinfunction "2_2") (pintype "passive"))
      (node (ref "R22") (pin "2") (pinfunction "2_2") (pintype "passive"))
      (node (ref "R23") (pin "2") (pinfunction "2_2") (pintype "passive"))
      (node (ref "R25") (pin "1") (pinfunction "1_1") (pintype "passive"))
      (node (ref "R30") (pin "1") (pinfunction "1_1") (pintype "passive"))
      (node (ref "U1") (pin "5") (pinfunction "VOUT_5") (pintype "passive"))
    )
    (net (code "73") (name "VCC5") (class "Default")
      (node (ref "C15") (pin "2") (pinfunction "2_2") (pintype "passive"))
      (node (ref "C16") (pin "1") (pinfunction "1_1") (pintype "passive"))
      (node (ref "C17") (pin "2") (pinfunction "2_2") (pintype "passive"))
      (node (ref "C4") (pin "2") (pinfunction "2_2") (pintype "passive"))
      (node (ref "D1") (pin "1") (pinfunction "1_1") (pintype "passive"))
      (node (ref "D9") (pin "2") (pinfunction "2_2") (pintype "passive"))
      (node (ref "J14") (pin "7") (pinfunction "7_7") (pintype "passive"))
      (node (ref "J14") (pin "8") (pinfunction "8_8") (pintype "passive"))
      (node (ref "J4") (pin "4") (pinfunction "4_4") (pintype "passive"))
      (node (ref "J7") (pin "1") (pinfunction "1_1") (pintype "passive"))
      (node (ref "J7") (pin "2") (pinfunction "2_2") (pintype "passive"))
      (node (ref "J7") (pin "3") (pinfunction "3_3") (pintype "passive"))
      (node (ref "J7") (pin "4") (pinfunction "4_4") (pintype "passive"))
      (node (ref "LS1") (pin "1") (pinfunction "1_1") (pintype "passive"))
      (node (ref "R13") (pin "2") (pinfunction "2_2") (pintype "passive"))
      (node (ref "R26") (pin "1") (pinfunction "1_1") (pintype "passive"))
      (node (ref "R27") (pin "1") (pinfunction "1_1") (pintype "passive"))
      (node (ref "R28") (pin "1") (pinfunction "1_1") (pintype "passive"))
      (node (ref "R29") (pin "1") (pinfunction "1_1") (pintype "passive"))
      (node (ref "U2") (pin "8") (pinfunction "VCC_8") (pintype "passive"))
      (node (ref "U3") (pin "1") (pinfunction "1_1") (pintype "passive"))
      (node (ref "U3") (pin "4") (pinfunction "4_4") (pintype "passive"))
      (node (ref "U6") (pin "1") (pinfunction "1_1") (pintype "passive"))
      (node (ref "U6") (pin "4") (pinfunction "4_4") (pintype "passive"))
      (node (ref "U7") (pin "1") (pinfunction "1_1") (pintype "passive"))
      (node (ref "U7") (pin "4") (pinfunction "4_4") (pintype "passive"))
    )
    (net (code "74") (name "unconnected-(J10-Pad7)") (class "Default")
      (node (ref "J10") (pin "7") (pinfunction "7_7") (pintype "passive+no_connect"))
    )
    (net (code "75") (name "unconnected-(J10-Pad8)") (class "Default")
      (node (ref "J10") (pin "8") (pinfunction "8_8") (pintype "passive+no_connect"))
    )
    (net (code "76") (name "unconnected-(J10-Pad9)") (class "Default")
      (node (ref "J10") (pin "9") (pinfunction "9_9") (pintype "passive+no_connect"))
    )
    (net (code "77") (name "unconnected-(J10-Pad10)") (class "Default")
      (node (ref "J10") (pin "10") (pinfunction "10_10") (pintype "passive+no_connect"))
    )
    (net (code "78") (name "unconnected-(J11-Pad8)") (class "Default")
      (node (ref "J11") (pin "8") (pinfunction "8_8") (pintype "passive+no_connect"))
    )
    (net (code "79") (name "unconnected-(J11-Pad10)") (class "Default")
      (node (ref "J11") (pin "10") (pinfunction "10_10") (pintype "passive+no_connect"))
    )
    (net (code "80") (name "unconnected-(J11-Pad13)") (class "Default")
      (node (ref "J11") (pin "13") (pinfunction "13_13") (pintype "passive+no_connect"))
    )
    (net (code "81") (name "unconnected-(J11-Pad14)") (class "Default")
      (node (ref "J11") (pin "14") (pinfunction "14_14") (pintype "passive+no_connect"))
    )
    (net (code "82") (name "unconnected-(J11-Pad15)") (class "Default")
      (node (ref "J11") (pin "15") (pinfunction "15_15") (pintype "passive+no_connect"))
    )
    (net (code "83") (name "unconnected-(J11-Pad17)") (class "Default")
      (node (ref "J11") (pin "17") (pinfunction "17_17") (pintype "passive+no_connect"))
    )
    (net (code "84") (name "unconnected-(J11-Pad18)") (class "Default")
      (node (ref "J11") (pin "18") (pinfunction "18_18") (pintype "passive+no_connect"))
    )
    (net (code "85") (name "unconnected-(J11-Pad19)") (class "Default")
      (node (ref "J11") (pin "19") (pinfunction "19_19") (pintype "passive+no_connect"))
    )
    (net (code "86") (name "unconnected-(J11-Pad20)") (class "Default")
      (node (ref "J11") (pin "20") (pinfunction "20_20") (pintype "passive+no_connect"))
    )
    (net (code "87") (name "unconnected-(J12-Pad11)") (class "Default")
      (node (ref "J12") (pin "11") (pinfunction "11_11") (pintype "passive+no_connect"))
    )
    (net (code "88") (name "unconnected-(J12-Pad12)") (class "Default")
      (node (ref "J12") (pin "12") (pinfunction "12_12") (pintype "passive+no_connect"))
    )
    (net (code "89") (name "unconnected-(J12-Pad13)") (class "Default")
      (node (ref "J12") (pin "13") (pinfunction "13_13") (pintype "passive+no_connect"))
    )
    (net (code "90") (name "unconnected-(J12-Pad14)") (class "Default")
      (node (ref "J12") (pin "14") (pinfunction "14_14") (pintype "passive+no_connect"))
    )
    (net (code "91") (name "unconnected-(J12-Pad15)") (class "Default")
      (node (ref "J12") (pin "15") (pinfunction "15_15") (pintype "passive+no_connect"))
    )
    (net (code "92") (name "unconnected-(J12-Pad16)") (class "Default")
      (node (ref "J12") (pin "16") (pinfunction "16_16") (pintype "passive+no_connect"))
    )
    (net (code "93") (name "unconnected-(R24-Pad1)") (class "Default")
      (node (ref "R24") (pin "1") (pinfunction "1_1") (pintype "passive"))
    )
    (net (code "94") (name "unconnected-(U1-NR{slash}FB-Pad4)") (class "Default")
      (node (ref "U1") (pin "4") (pinfunction "NR/FB_4") (pintype "passive"))
    )
    (net (code "95") (name "unconnected-(U2-OSC-Pad7)") (class "Default")
      (node (ref "U2") (pin "7") (pinfunction "OSC_7") (pintype "passive"))
    )
  )
)
